# IOP_1_2.net
KiCad netlist of a schematic drawn in EAGLE
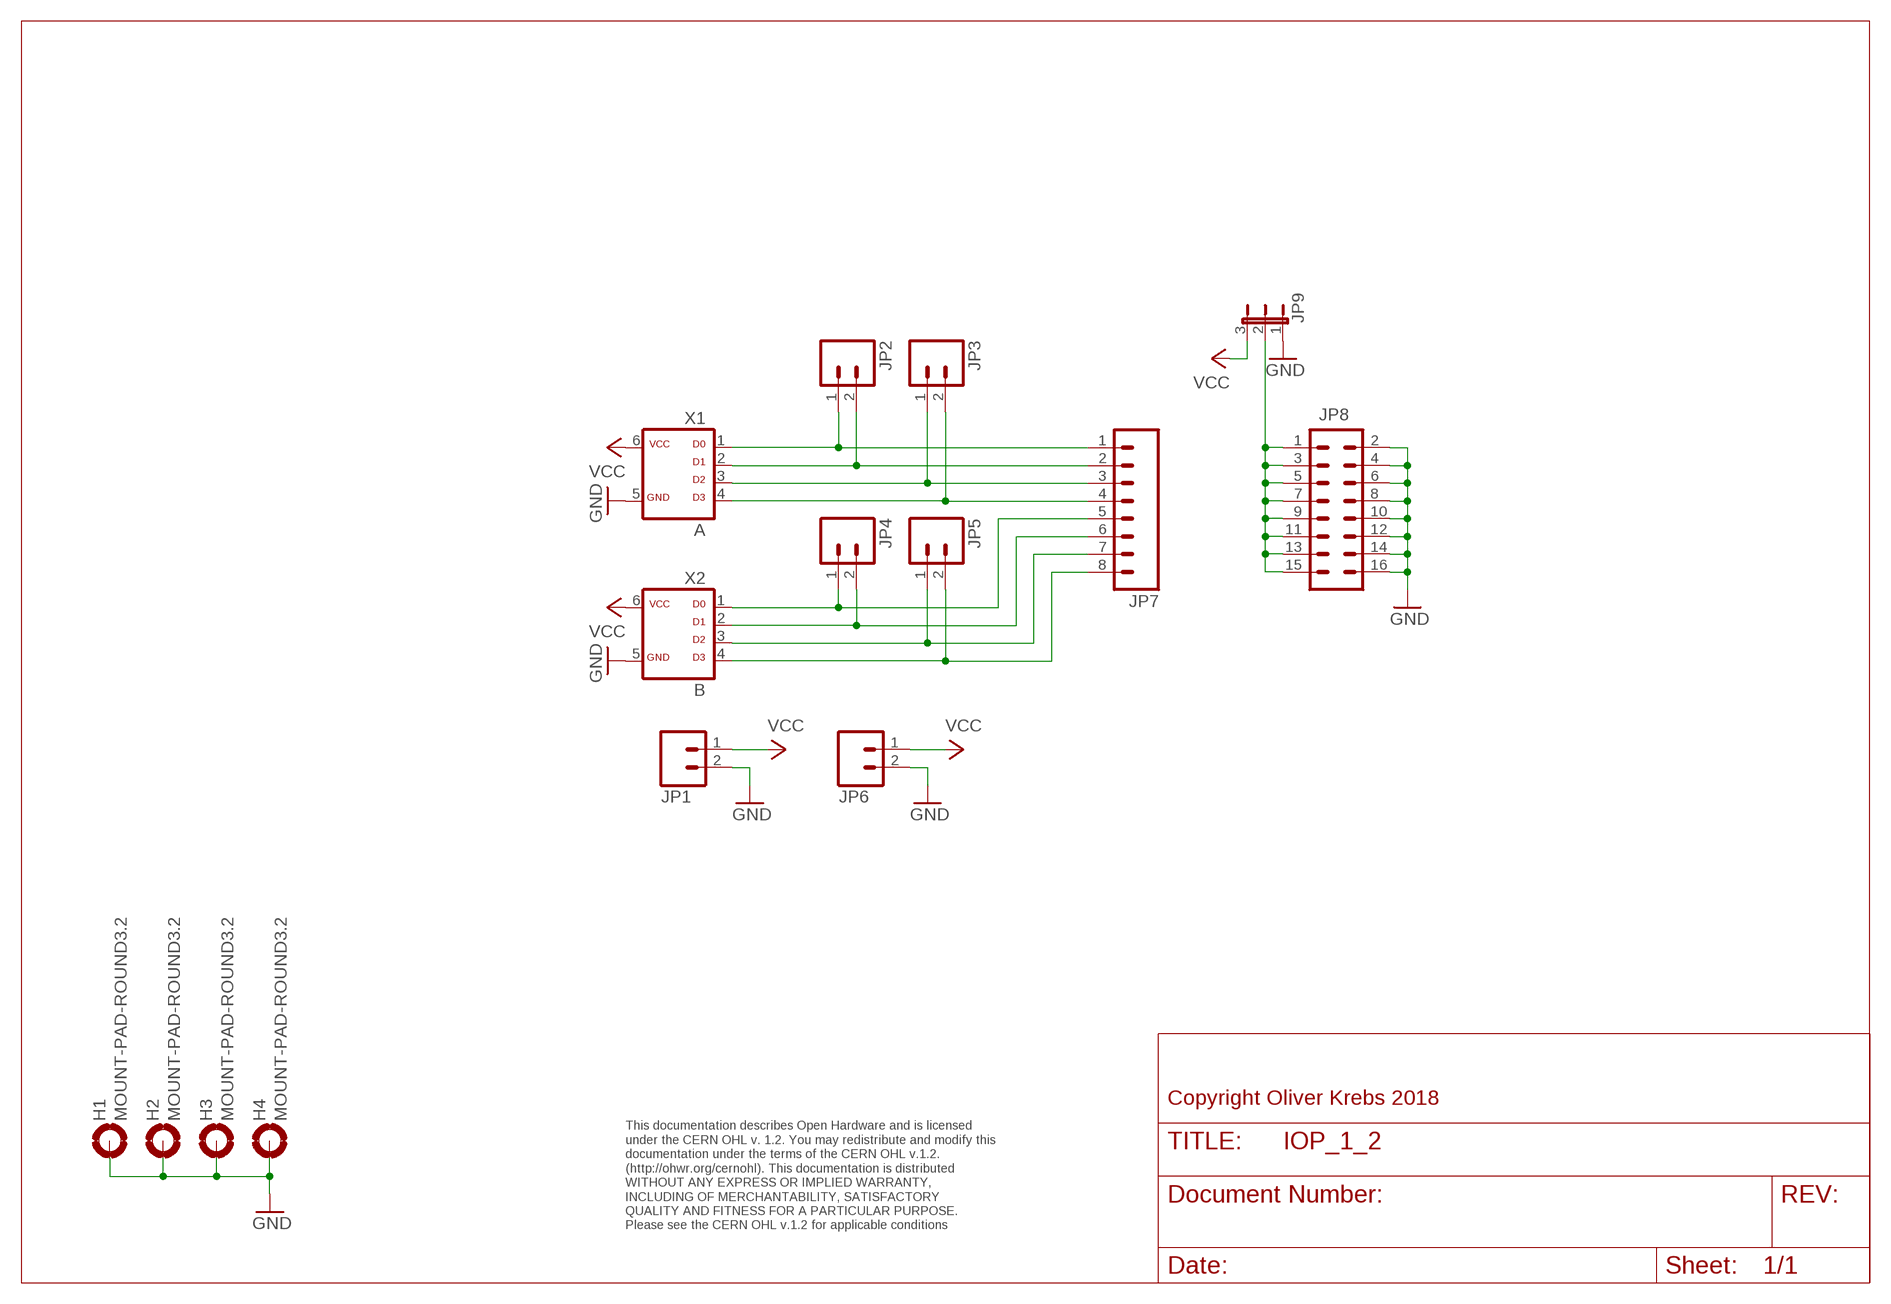
[diagram p0: schematic, sheet 1]

(export (version "E")
  (design (tool "Eeschema 10.0.6"))
  (components
    (comp (ref "H1")
      (value "MOUNT-PAD-ROUND3.2")
      (footprint "eagle-import:3,2-PAD")
      (libsource (lib "eagle-import") (part "MOUNT-PAD-ROUND3.2"))
    )
    (comp (ref "H2")
      (value "MOUNT-PAD-ROUND3.2")
      (footprint "eagle-import:3,2-PAD")
      (libsource (lib "eagle-import") (part "MOUNT-PAD-ROUND3.2"))
    )
    (comp (ref "H3")
      (value "MOUNT-PAD-ROUND3.2")
      (footprint "eagle-import:3,2-PAD")
      (libsource (lib "eagle-import") (part "MOUNT-PAD-ROUND3.2"))
    )
    (comp (ref "H4")
      (value "MOUNT-PAD-ROUND3.2")
      (footprint "eagle-import:3,2-PAD")
      (libsource (lib "eagle-import") (part "MOUNT-PAD-ROUND3.2"))
    )
    (comp (ref "JP1")
      (value "M021.3MM-5.08")
      (footprint "eagle-import:1X02_BIG_5.08")
      (libsource (lib "eagle-import") (part "M021.3MM-5.08"))
    )
    (comp (ref "JP2")
      (value "M021.3MM-5.08")
      (footprint "eagle-import:1X02_BIG_5.08")
      (libsource (lib "eagle-import") (part "M021.3MM-5.08"))
    )
    (comp (ref "JP3")
      (value "M021.3MM-5.08")
      (footprint "eagle-import:1X02_BIG_5.08")
      (libsource (lib "eagle-import") (part "M021.3MM-5.08"))
    )
    (comp (ref "JP4")
      (value "M021.3MM-5.08")
      (footprint "eagle-import:1X02_BIG_5.08")
      (libsource (lib "eagle-import") (part "M021.3MM-5.08"))
    )
    (comp (ref "JP5")
      (value "M021.3MM-5.08")
      (footprint "eagle-import:1X02_BIG_5.08")
      (libsource (lib "eagle-import") (part "M021.3MM-5.08"))
    )
    (comp (ref "JP6")
      (value "M021.3MM-5.08")
      (footprint "eagle-import:1X02_BIG_5.08")
      (libsource (lib "eagle-import") (part "M021.3MM-5.08"))
    )
    (comp (ref "JP7")
      (value "M08")
      (footprint "eagle-import:1X08_ROUND")
      (libsource (lib "eagle-import") (part "M08"))
    )
    (comp (ref "JP8")
      (value "M08X2")
      (footprint "eagle-import:2X8")
      (libsource (lib "eagle-import") (part "M08X2"))
    )
    (comp (ref "JP9")
      (value "JP2EJP2-U")
      (footprint "eagle-import:JP2-U")
      (libsource (lib "eagle-import") (part "JP2EJP2-U"))
    )
    (comp (ref "X1")
      (value "A")
      (footprint "eagle-import:ML-6")
      (libsource (lib "eagle-import") (part "ML6D"))
    )
    (comp (ref "X2")
      (value "B")
      (footprint "eagle-import:ML-6")
      (libsource (lib "eagle-import") (part "ML6D"))
    )
  )
  (nets
    (net (code "1") (name "GND") (class "Default")
      (node (ref "H1") (pin "B3,2") (pinfunction "MOUNT_B3,2") (pintype "passive"))
      (node (ref "H2") (pin "B3,2") (pinfunction "MOUNT_B3,2") (pintype "passive"))
      (node (ref "H3") (pin "B3,2") (pinfunction "MOUNT_B3,2") (pintype "passive"))
      (node (ref "H4") (pin "B3,2") (pinfunction "MOUNT_B3,2") (pintype "passive"))
      (node (ref "JP1") (pin "2") (pinfunction "2_2") (pintype "passive"))
      (node (ref "JP6") (pin "2") (pinfunction "2_2") (pintype "passive"))
      (node (ref "JP8") (pin "10") (pinfunction "10_10") (pintype "passive"))
      (node (ref "JP8") (pin "12") (pinfunction "12_12") (pintype "passive"))
      (node (ref "JP8") (pin "14") (pinfunction "14_14") (pintype "passive"))
      (node (ref "JP8") (pin "16") (pinfunction "16_16") (pintype "passive"))
      (node (ref "JP8") (pin "2") (pinfunction "2_2") (pintype "passive"))
      (node (ref "JP8") (pin "4") (pinfunction "4_4") (pintype "passive"))
      (node (ref "JP8") (pin "6") (pinfunction "6_6") (pintype "passive"))
      (node (ref "JP8") (pin "8") (pinfunction "8_8") (pintype "passive"))
      (node (ref "JP9") (pin "1") (pinfunction "1_1") (pintype "passive"))
      (node (ref "X1") (pin "5") (pinfunction "5_5") (pintype "passive"))
      (node (ref "X2") (pin "5") (pinfunction "5_5") (pintype "passive"))
    )
    (net (code "2") (name "Net-(JP2-Pad1)") (class "Default")
      (node (ref "JP2") (pin "1") (pinfunction "1_1") (pintype "passive"))
      (node (ref "JP7") (pin "1") (pinfunction "1_1") (pintype "passive"))
      (node (ref "X1") (pin "1") (pinfunction "1_1") (pintype "passive"))
    )
    (net (code "3") (name "Net-(JP2-Pad2)") (class "Default")
      (node (ref "JP2") (pin "2") (pinfunction "2_2") (pintype "passive"))
      (node (ref "JP7") (pin "2") (pinfunction "2_2") (pintype "passive"))
      (node (ref "X1") (pin "2") (pinfunction "2_2") (pintype "passive"))
    )
    (net (code "4") (name "Net-(JP3-Pad1)") (class "Default")
      (node (ref "JP3") (pin "1") (pinfunction "1_1") (pintype "passive"))
      (node (ref "JP7") (pin "3") (pinfunction "3_3") (pintype "passive"))
      (node (ref "X1") (pin "3") (pinfunction "3_3") (pintype "passive"))
    )
    (net (code "5") (name "Net-(JP3-Pad2)") (class "Default")
      (node (ref "JP3") (pin "2") (pinfunction "2_2") (pintype "passive"))
      (node (ref "JP7") (pin "4") (pinfunction "4_4") (pintype "passive"))
      (node (ref "X1") (pin "4") (pinfunction "4_4") (pintype "passive"))
    )
    (net (code "6") (name "Net-(JP4-Pad1)") (class "Default")
      (node (ref "JP4") (pin "1") (pinfunction "1_1") (pintype "passive"))
      (node (ref "JP7") (pin "5") (pinfunction "5_5") (pintype "passive"))
      (node (ref "X2") (pin "1") (pinfunction "1_1") (pintype "passive"))
    )
    (net (code "7") (name "Net-(JP4-Pad2)") (class "Default")
      (node (ref "JP4") (pin "2") (pinfunction "2_2") (pintype "passive"))
      (node (ref "JP7") (pin "6") (pinfunction "6_6") (pintype "passive"))
      (node (ref "X2") (pin "2") (pinfunction "2_2") (pintype "passive"))
    )
    (net (code "8") (name "Net-(JP5-Pad1)") (class "Default")
      (node (ref "JP5") (pin "1") (pinfunction "1_1") (pintype "passive"))
      (node (ref "JP7") (pin "7") (pinfunction "7_7") (pintype "passive"))
      (node (ref "X2") (pin "3") (pinfunction "3_3") (pintype "passive"))
    )
    (net (code "9") (name "Net-(JP5-Pad2)") (class "Default")
      (node (ref "JP5") (pin "2") (pinfunction "2_2") (pintype "passive"))
      (node (ref "JP7") (pin "8") (pinfunction "8_8") (pintype "passive"))
      (node (ref "X2") (pin "4") (pinfunction "4_4") (pintype "passive"))
    )
    (net (code "10") (name "Net-(JP8-Pad1)") (class "Default")
      (node (ref "JP8") (pin "1") (pinfunction "1_1") (pintype "passive"))
      (node (ref "JP8") (pin "11") (pinfunction "11_11") (pintype "passive"))
      (node (ref "JP8") (pin "13") (pinfunction "13_13") (pintype "passive"))
      (node (ref "JP8") (pin "15") (pinfunction "15_15") (pintype "passive"))
      (node (ref "JP8") (pin "3") (pinfunction "3_3") (pintype "passive"))
      (node (ref "JP8") (pin "5") (pinfunction "5_5") (pintype "passive"))
      (node (ref "JP8") (pin "7") (pinfunction "7_7") (pintype "passive"))
      (node (ref "JP8") (pin "9") (pinfunction "9_9") (pintype "passive"))
      (node (ref "JP9") (pin "2") (pinfunction "2_2") (pintype "passive"))
    )
    (net (code "11") (name "VCC") (class "Default")
      (node (ref "JP1") (pin "1") (pinfunction "1_1") (pintype "passive"))
      (node (ref "JP6") (pin "1") (pinfunction "1_1") (pintype "passive"))
      (node (ref "JP9") (pin "3") (pinfunction "3_3") (pintype "passive"))
      (node (ref "X1") (pin "6") (pinfunction "6_6") (pintype "passive"))
      (node (ref "X2") (pin "6") (pinfunction "6_6") (pintype "passive"))
    )
  )
)
